# EDU_High-Speed-Design_LED.net
KiCad netlist of a schematic drawn in Altium Designer
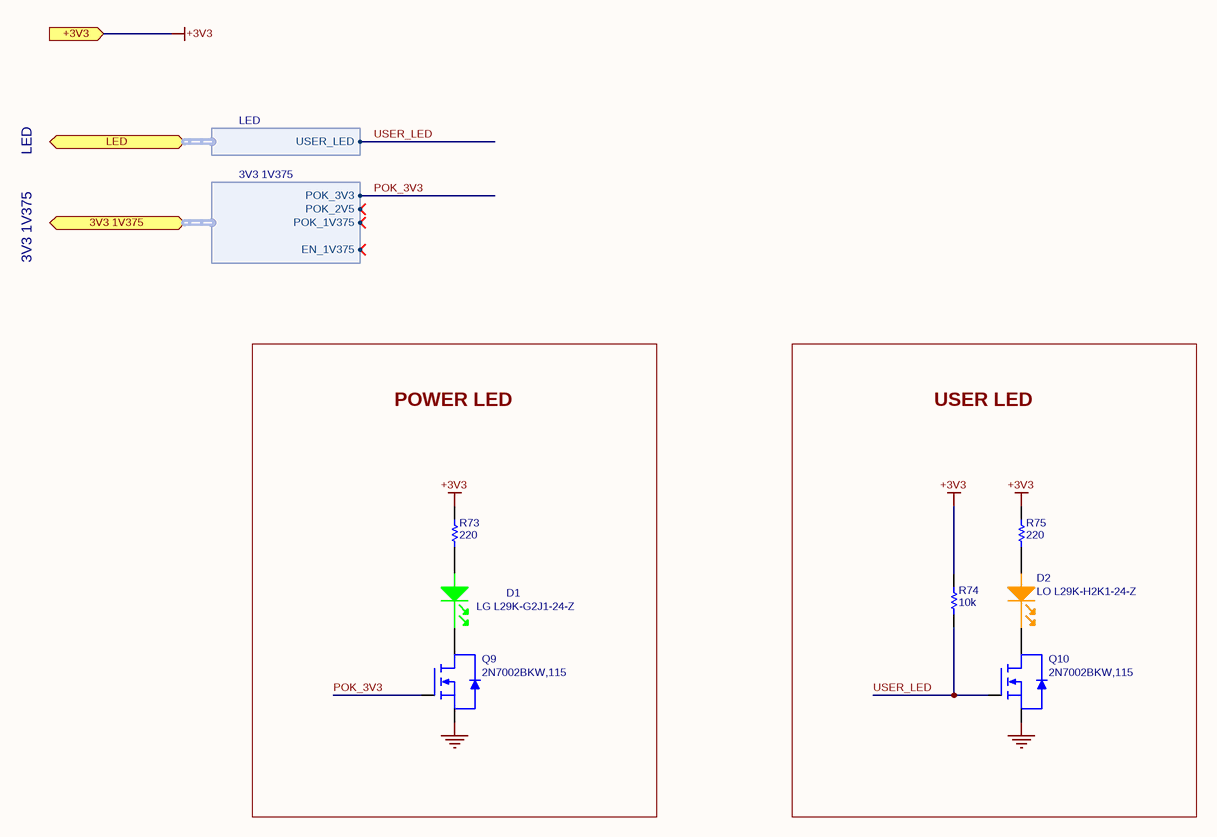
[diagram p0: EDU_High-Speed-Design_LED.SchDoc]

(export (version "E")
  (design (tool "Eeschema 10.0.6"))
  (components
    (comp (ref "D1")
      (value "LG L29K-G2J1-24-Z")
      (footprint "LED_0603_GREEN")
      (description "LED SMARTLED GREEN 570NM 0603")
      (libsource (lib "EDU_High-Speed-Design") (part "LG L29K-G2J1-24-Z"))
    )
    (comp (ref "D2")
      (value "LO L29K-H2K1-24-Z")
      (footprint "LED_0603_ORANGE")
      (description "LED SMARTLED ORANGE 606NM 0603")
      (libsource (lib "EDU_High-Speed-Design") (part "LO L29K-H2K1-24-Z"))
    )
    (comp (ref "Q9")
      (value "2N7002BKW,115")
      (footprint "SOT-23-3")
      (description "MOSFET N-CH 60V 310MA SOT323")
      (libsource (lib "EDU_High-Speed-Design") (part "2N7002BKW,115"))
    )
    (comp (ref "Q10")
      (value "2N7002BKW,115")
      (footprint "SOT-23-3")
      (description "MOSFET N-CH 60V 310MA SOT323")
      (libsource (lib "EDU_High-Speed-Design") (part "2N7002BKW,115"))
    )
    (comp (ref "R73")
      (value "220")
      (footprint "R0402")
      (description "RES 220 OHM 1/16W 1% 0402 SMD")
      (libsource (lib "EDU_High-Speed-Design") (part "RC0402FR-07220RL"))
    )
    (comp (ref "R74")
      (value "10k")
      (footprint "R0402")
      (description "RES 10.0K OHM 1/16W 1% 0402 SMD")
      (libsource (lib "EDU_High-Speed-Design") (part "RC0402FR-0710KL"))
    )
    (comp (ref "R75")
      (value "220")
      (footprint "R0402")
      (description "RES 220 OHM 1/16W 1% 0402 SMD")
      (libsource (lib "EDU_High-Speed-Design") (part "RC0402FR-07220RL"))
    )
  )
  (nets
    (net (code "4") (name "+3V3") (class "Default")
      (node (ref "R73") (pin "1") (pinfunction "1_1") (pintype "passive"))
      (node (ref "R74") (pin "2") (pinfunction "2_2") (pintype "passive"))
      (node (ref "R75") (pin "1") (pinfunction "1_1") (pintype "passive"))
    )
    (net (code "5") (name "/POK_3V3") (class "Default")
      (node (ref "Q9") (pin "1") (pinfunction "G_1") (pintype "passive"))
    )
    (net (code "6") (name "/USER_LED") (class "Default")
      (node (ref "Q10") (pin "1") (pinfunction "G_1") (pintype "passive"))
      (node (ref "R74") (pin "1") (pinfunction "1_1") (pintype "passive"))
    )
    (net (code "9") (name "GND") (class "Default")
      (node (ref "Q10") (pin "2") (pinfunction "S_2") (pintype "passive"))
      (node (ref "Q9") (pin "2") (pinfunction "S_2") (pintype "passive"))
    )
    (net (code "10") (name "Net-(D1-ANODE)") (class "Default")
      (node (ref "D1") (pin "2") (pinfunction "ANODE_2") (pintype "passive"))
      (node (ref "R73") (pin "2") (pinfunction "2_2") (pintype "passive"))
    )
    (net (code "11") (name "Net-(D1-cathode)") (class "Default")
      (node (ref "D1") (pin "1") (pinfunction "cathode_1") (pintype "passive"))
      (node (ref "Q9") (pin "3") (pinfunction "D_3") (pintype "passive"))
    )
    (net (code "12") (name "Net-(D2-ANODE)") (class "Default")
      (node (ref "D2") (pin "2") (pinfunction "ANODE_2") (pintype "passive"))
      (node (ref "R75") (pin "2") (pinfunction "2_2") (pintype "passive"))
    )
    (net (code "13") (name "Net-(D2-cathode)") (class "Default")
      (node (ref "D2") (pin "1") (pinfunction "cathode_1") (pintype "passive"))
      (node (ref "Q10") (pin "3") (pinfunction "D_3") (pintype "passive"))
    )
  )
)
